# 09-RTL8111H-2.net
KiCad netlist of a schematic drawn in Altium Designer
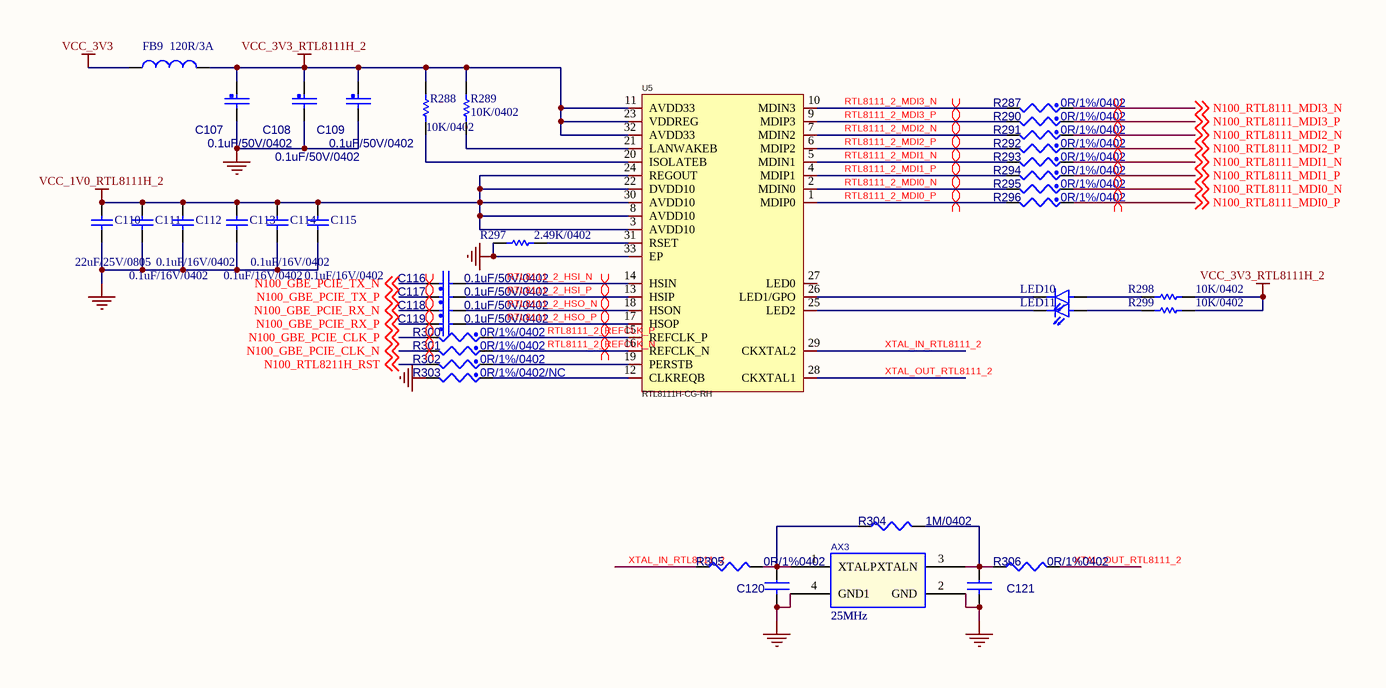
[diagram p0: 09-RTL8111H-2.schdoc]

(export (version "E")
  (design (tool "Eeschema 10.0.6"))
  (components
    (comp (ref "AX3")
      (value "25MHz")
      (footprint "2016")
      (fields (field (name "ALTIUM_VALUE") "25MHz"))
      (libsource (lib "*") (part "XTAL_0"))
    )
    (comp (ref "C107")
      (value "0.1uF/50V/0402")
      (footprint "C0402")
      (description "GCM155R71H104KE02/MURATA")
      (fields (field (name "TOLERANCE") "10%") (field (name "VOLTAGE") "16V"))
      (libsource (lib "*") (part "CAP_NP"))
    )
    (comp (ref "C108")
      (value "0.1uF/50V/0402")
      (footprint "C0402")
      (description "GCM155R71H104KE02/MURATA")
      (fields (field (name "TOLERANCE") "10%") (field (name "VOLTAGE") "16V"))
      (libsource (lib "*") (part "CAP_NP"))
    )
    (comp (ref "C109")
      (value "0.1uF/50V/0402")
      (footprint "C0402")
      (description "GCM155R71H104KE02/MURATA")
      (fields (field (name "TOLERANCE") "10%") (field (name "VOLTAGE") "16V"))
      (libsource (lib "*") (part "CAP_NP"))
    )
    (comp (ref "C110")
      (value "22uF/25V/0805")
      (description "Capacitor")
      (fields (field (name "PUBLISHER") "Altium Limited"))
      (libsource (lib "LIBS") (part "CAP"))
    )
    (comp (ref "C111")
      (value "0.1uF/16V/0402")
      (description "Capacitor")
      (fields (field (name "PUBLISHER") "Altium Limited"))
      (libsource (lib "LIBS") (part "CAP"))
    )
    (comp (ref "C112")
      (value "0.1uF/16V/0402")
      (description "Capacitor")
      (fields (field (name "PUBLISHER") "Altium Limited"))
      (libsource (lib "LIBS") (part "CAP"))
    )
    (comp (ref "C113")
      (value "0.1uF/16V/0402")
      (description "Capacitor")
      (fields (field (name "PUBLISHER") "Altium Limited"))
      (libsource (lib "LIBS") (part "CAP"))
    )
    (comp (ref "C114")
      (value "0.1uF/16V/0402")
      (description "Capacitor")
      (fields (field (name "PUBLISHER") "Altium Limited"))
      (libsource (lib "LIBS") (part "CAP"))
    )
    (comp (ref "C115")
      (value "0.1uF/16V/0402")
      (description "Capacitor")
      (fields (field (name "PUBLISHER") "Altium Limited"))
      (libsource (lib "LIBS") (part "CAP"))
    )
    (comp (ref "C116")
      (value "0.1uF/50V/0402")
      (footprint "C0402")
      (description "GCM155R71H104KE02/MURATA")
      (fields (field (name "TOLERANCE") "10%") (field (name "VOLTAGE") "16V"))
      (libsource (lib "*") (part "CAP_NP"))
    )
    (comp (ref "C117")
      (value "0.1uF/50V/0402")
      (footprint "C0402")
      (description "GCM155R71H104KE02/MURATA")
      (fields (field (name "TOLERANCE") "10%") (field (name "VOLTAGE") "16V"))
      (libsource (lib "*") (part "CAP_NP"))
    )
    (comp (ref "C118")
      (value "0.1uF/50V/0402")
      (footprint "C0402")
      (description "GCM155R71H104KE02/MURATA")
      (fields (field (name "TOLERANCE") "10%") (field (name "VOLTAGE") "16V"))
      (libsource (lib "*") (part "CAP_NP"))
    )
    (comp (ref "C119")
      (value "0.1uF/50V/0402")
      (footprint "C0402")
      (description "GCM155R71H104KE02/MURATA")
      (fields (field (name "TOLERANCE") "10%") (field (name "VOLTAGE") "16V"))
      (libsource (lib "*") (part "CAP_NP"))
    )
    (comp (ref "C120") (value "CAP NP_Dup3") (footprint "C0402") (libsource (lib "*") (part "CAP NP_Dup3")))
    (comp (ref "C121") (value "CAP NP_Dup3") (footprint "C0402") (libsource (lib "*") (part "CAP NP_Dup3")))
    (comp (ref "FB9")
      (value "120R/3A")
      (footprint "L0603")
      (description "BLM18KG121TN1D")
      (fields (field (name "PUBLISHER") "Altium Limited"))
      (libsource (lib "LIBS") (part "Inductor"))
    )
    (comp (ref "LED10") (value "LED_GREEN") (footprint "LED0603") (libsource (lib "LIBS") (part "LED")))
    (comp (ref "LED11") (value "LED_GREEN") (footprint "LED0603") (libsource (lib "LIBS") (part "LED")))
    (comp (ref "R287")
      (value "0R/1%/0402")
      (footprint "R0402")
      (description "AC0402FR-070RL/YAGEO")
      (fields (field (name "TOLERANCE") "1%") (field (name "Comment") "RES_Dup2"))
      (libsource (lib "*") (part "RES_Dup2"))
    )
    (comp (ref "R288")
      (value "10K/0402")
      (footprint "R0402")
      (description "Semiconductor Resistor")
      (fields (field (name "PUBLISHER") "Altium Limited"))
      (libsource (lib "LIBS") (part "Res Semi"))
    )
    (comp (ref "R289")
      (value "10K/0402")
      (footprint "R0402")
      (description "Semiconductor Resistor")
      (fields (field (name "PUBLISHER") "Altium Limited"))
      (libsource (lib "LIBS") (part "Res Semi"))
    )
    (comp (ref "R290")
      (value "0R/1%/0402")
      (footprint "R0402")
      (description "AC0402FR-070RL/YAGEO")
      (fields (field (name "TOLERANCE") "1%") (field (name "Comment") "RES_Dup2"))
      (libsource (lib "*") (part "RES_Dup2"))
    )
    (comp (ref "R291")
      (value "0R/1%/0402")
      (footprint "R0402")
      (description "AC0402FR-070RL/YAGEO")
      (fields (field (name "TOLERANCE") "1%") (field (name "Comment") "RES_Dup2"))
      (libsource (lib "*") (part "RES_Dup2"))
    )
    (comp (ref "R292")
      (value "0R/1%/0402")
      (footprint "R0402")
      (description "AC0402FR-070RL/YAGEO")
      (fields (field (name "TOLERANCE") "1%") (field (name "Comment") "RES_Dup2"))
      (libsource (lib "*") (part "RES_Dup2"))
    )
    (comp (ref "R293")
      (value "0R/1%/0402")
      (footprint "R0402")
      (description "AC0402FR-070RL/YAGEO")
      (fields (field (name "TOLERANCE") "1%") (field (name "Comment") "RES_Dup2"))
      (libsource (lib "*") (part "RES_Dup2"))
    )
    (comp (ref "R294")
      (value "0R/1%/0402")
      (footprint "R0402")
      (description "AC0402FR-070RL/YAGEO")
      (fields (field (name "TOLERANCE") "1%") (field (name "Comment") "RES_Dup2"))
      (libsource (lib "*") (part "RES_Dup2"))
    )
    (comp (ref "R295")
      (value "0R/1%/0402")
      (footprint "R0402")
      (description "AC0402FR-070RL/YAGEO")
      (fields (field (name "TOLERANCE") "1%") (field (name "Comment") "RES_Dup2"))
      (libsource (lib "*") (part "RES_Dup2"))
    )
    (comp (ref "R296")
      (value "0R/1%/0402")
      (footprint "R0402")
      (description "AC0402FR-070RL/YAGEO")
      (fields (field (name "TOLERANCE") "1%") (field (name "Comment") "RES_Dup2"))
      (libsource (lib "*") (part "RES_Dup2"))
    )
    (comp (ref "R297")
      (value "2.49K/0402")
      (footprint "R0402")
      (description "Semiconductor Resistor")
      (fields (field (name "PUBLISHER") "Altium Limited"))
      (libsource (lib "LIBS") (part "Res Semi"))
    )
    (comp (ref "R298")
      (value "10K/0402")
      (footprint "R0402")
      (description "Semiconductor Resistor")
      (fields (field (name "PUBLISHER") "Altium Limited"))
      (libsource (lib "LIBS") (part "Res Semi"))
    )
    (comp (ref "R299")
      (value "10K/0402")
      (footprint "R0402")
      (description "Semiconductor Resistor")
      (fields (field (name "PUBLISHER") "Altium Limited"))
      (libsource (lib "LIBS") (part "Res Semi"))
    )
    (comp (ref "R300")
      (value "0R/1%/0402")
      (footprint "R0402")
      (description "AC0402FR-070RL/YAGEO")
      (fields (field (name "TOLERANCE") "1%") (field (name "Comment") "RES_Dup2"))
      (libsource (lib "*") (part "RES_Dup2"))
    )
    (comp (ref "R301")
      (value "0R/1%/0402")
      (footprint "R0402")
      (description "AC0402FR-070RL/YAGEO")
      (fields (field (name "TOLERANCE") "1%") (field (name "Comment") "RES_Dup2"))
      (libsource (lib "*") (part "RES_Dup2"))
    )
    (comp (ref "R302")
      (value "0R/1%/0402")
      (footprint "R0402")
      (description "AC0402FR-070RL/YAGEO")
      (fields (field (name "TOLERANCE") "1%") (field (name "Comment") "RES_Dup2"))
      (libsource (lib "*") (part "RES_Dup2"))
    )
    (comp (ref "R303")
      (value "0R/1%/0402/NC")
      (footprint "R0402")
      (description "AC0402FR-070RL/YAGEO")
      (fields (field (name "TOLERANCE") "1%") (field (name "Comment") "RES_Dup2"))
      (libsource (lib "*") (part "RES_Dup2"))
    )
    (comp (ref "R304")
      (value "1M/0402")
      (footprint "R0402")
      (fields (field (name "Comment") "R_Dup3"))
      (libsource (lib "*") (part "R_Dup3"))
    )
    (comp (ref "R305")
      (value "0R/1%0402")
      (footprint "R0402")
      (fields (field (name "Comment") "R_Dup3"))
      (libsource (lib "*") (part "R_Dup3"))
    )
    (comp (ref "R306")
      (value "0R/1%0402")
      (footprint "R0402")
      (fields (field (name "Comment") "R_Dup3"))
      (libsource (lib "*") (part "R_Dup3"))
    )
    (comp (ref "U5")
      (value "RTL8111H-CG-RH")
      (footprint "RTL8111H-CG-RH")
      (fields (field (name "MANUFACTURER") "REALTEK(瑞昱)") (field (name "MANUFACTURER PART") "RTL8111H-CG"))
      (libsource (lib "17267508141_1726750814") (part "RTL8111H-CG"))
    )
  )
  (nets
    (net (code "1") (name "/RTL8111_2_HSI_N") (class "Default")
      (node (ref "C116") (pin "2") (pinfunction "2_2") (pintype "passive"))
      (node (ref "U5") (pin "14") (pinfunction "HSIN_14") (pintype "passive"))
    )
    (net (code "2") (name "/RTL8111_2_HSI_P") (class "Default")
      (node (ref "C117") (pin "2") (pinfunction "2_2") (pintype "passive"))
      (node (ref "U5") (pin "13") (pinfunction "HSIP_13") (pintype "passive"))
    )
    (net (code "3") (name "/RTL8111_2_HSO_N") (class "Default")
      (node (ref "C118") (pin "2") (pinfunction "2_2") (pintype "passive"))
      (node (ref "U5") (pin "18") (pinfunction "HSON_18") (pintype "passive"))
    )
    (net (code "4") (name "/RTL8111_2_HSO_P") (class "Default")
      (node (ref "C119") (pin "2") (pinfunction "2_2") (pintype "passive"))
      (node (ref "U5") (pin "17") (pinfunction "HSOP_17") (pintype "passive"))
    )
    (net (code "5") (name "/RTL8111_2_MDI0_N") (class "Default")
      (node (ref "R295") (pin "2") (pinfunction "2_2") (pintype "passive"))
      (node (ref "U5") (pin "2") (pinfunction "MDIN0_2") (pintype "passive"))
    )
    (net (code "6") (name "/RTL8111_2_MDI0_P") (class "Default")
      (node (ref "R296") (pin "2") (pinfunction "2_2") (pintype "passive"))
      (node (ref "U5") (pin "1") (pinfunction "MDIP0_1") (pintype "passive"))
    )
    (net (code "7") (name "/RTL8111_2_MDI1_N") (class "Default")
      (node (ref "R293") (pin "2") (pinfunction "2_2") (pintype "passive"))
      (node (ref "U5") (pin "5") (pinfunction "MDIN1_5") (pintype "passive"))
    )
    (net (code "8") (name "/RTL8111_2_MDI1_P") (class "Default")
      (node (ref "R294") (pin "2") (pinfunction "2_2") (pintype "passive"))
      (node (ref "U5") (pin "4") (pinfunction "MDIP1_4") (pintype "passive"))
    )
    (net (code "9") (name "/RTL8111_2_MDI2_N") (class "Default")
      (node (ref "R291") (pin "2") (pinfunction "2_2") (pintype "passive"))
      (node (ref "U5") (pin "7") (pinfunction "MDIN2_7") (pintype "passive"))
    )
    (net (code "10") (name "/RTL8111_2_MDI2_P") (class "Default")
      (node (ref "R292") (pin "2") (pinfunction "2_2") (pintype "passive"))
      (node (ref "U5") (pin "6") (pinfunction "MDIP2_6") (pintype "passive"))
    )
    (net (code "11") (name "/RTL8111_2_MDI3_N") (class "Default")
      (node (ref "R287") (pin "2") (pinfunction "2_2") (pintype "passive"))
      (node (ref "U5") (pin "10") (pinfunction "MDIN3_10") (pintype "passive"))
    )
    (net (code "12") (name "/RTL8111_2_MDI3_P") (class "Default")
      (node (ref "R290") (pin "2") (pinfunction "2_2") (pintype "passive"))
      (node (ref "U5") (pin "9") (pinfunction "MDIP3_9") (pintype "passive"))
    )
    (net (code "13") (name "/RTL8111_2_REFCLK_N") (class "Default")
      (node (ref "R301") (pin "1") (pinfunction "1_1") (pintype "passive"))
      (node (ref "U5") (pin "16") (pinfunction "REFCLK_N_16") (pintype "passive"))
    )
    (net (code "14") (name "/RTL8111_2_REFCLK_P") (class "Default")
      (node (ref "R300") (pin "1") (pinfunction "1_1") (pintype "passive"))
      (node (ref "U5") (pin "15") (pinfunction "REFCLK_P_15") (pintype "passive"))
    )
    (net (code "15") (name "/XTAL_IN_RTL8111_2") (class "Default")
      (node (ref "R305") (pin "1") (pinfunction "1_1") (pintype "passive"))
      (node (ref "U5") (pin "29") (pinfunction "CKXTAL2_29") (pintype "passive"))
    )
    (net (code "16") (name "/XTAL_OUT_RTL8111_2") (class "Default")
      (node (ref "R306") (pin "2") (pinfunction "2_2") (pintype "passive"))
      (node (ref "U5") (pin "28") (pinfunction "CKXTAL1_28") (pintype "passive"))
    )
    (net (code "17") (name "GND") (class "Default")
      (node (ref "AX3") (pin "2") (pinfunction "GND_2") (pintype "passive"))
      (node (ref "AX3") (pin "4") (pinfunction "GND1_4") (pintype "passive"))
      (node (ref "C107") (pin "2") (pinfunction "2_2") (pintype "passive"))
      (node (ref "C108") (pin "2") (pinfunction "2_2") (pintype "passive"))
      (node (ref "C109") (pin "2") (pinfunction "2_2") (pintype "passive"))
      (node (ref "C110") (pin "1") (pinfunction "1_1") (pintype "passive"))
      (node (ref "C111") (pin "1") (pinfunction "1_1") (pintype "passive"))
      (node (ref "C112") (pin "1") (pinfunction "1_1") (pintype "passive"))
      (node (ref "C113") (pin "1") (pinfunction "1_1") (pintype "passive"))
      (node (ref "C114") (pin "1") (pinfunction "1_1") (pintype "passive"))
      (node (ref "C115") (pin "1") (pinfunction "1_1") (pintype "passive"))
      (node (ref "C120") (pin "2") (pinfunction "2_2") (pintype "passive"))
      (node (ref "C121") (pin "2") (pinfunction "2_2") (pintype "passive"))
      (node (ref "R297") (pin "1") (pinfunction "1_1") (pintype "passive"))
      (node (ref "R303") (pin "2") (pinfunction "2_2") (pintype "passive"))
      (node (ref "U5") (pin "33") (pinfunction "EP_33") (pintype "passive"))
    )
    (net (code "18") (name "N100_GBE_PCIE_CLK_N") (class "Default")
      (node (ref "R301") (pin "2") (pinfunction "2_2") (pintype "passive"))
    )
    (net (code "19") (name "N100_GBE_PCIE_CLK_P") (class "Default")
      (node (ref "R300") (pin "2") (pinfunction "2_2") (pintype "passive"))
    )
    (net (code "20") (name "N100_GBE_PCIE_RX_N") (class "Default")
      (node (ref "C118") (pin "1") (pinfunction "1_1") (pintype "passive"))
    )
    (net (code "21") (name "N100_GBE_PCIE_RX_P") (class "Default")
      (node (ref "C119") (pin "1") (pinfunction "1_1") (pintype "passive"))
    )
    (net (code "22") (name "N100_GBE_PCIE_TX_N") (class "Default")
      (node (ref "C116") (pin "1") (pinfunction "1_1") (pintype "passive"))
    )
    (net (code "23") (name "N100_GBE_PCIE_TX_P") (class "Default")
      (node (ref "C117") (pin "1") (pinfunction "1_1") (pintype "passive"))
    )
    (net (code "24") (name "N100_RTL8111_MDI0_N") (class "Default")
      (node (ref "R295") (pin "1") (pinfunction "1_1") (pintype "passive"))
    )
    (net (code "25") (name "N100_RTL8111_MDI0_P") (class "Default")
      (node (ref "R296") (pin "1") (pinfunction "1_1") (pintype "passive"))
    )
    (net (code "26") (name "N100_RTL8111_MDI1_N") (class "Default")
      (node (ref "R293") (pin "1") (pinfunction "1_1") (pintype "passive"))
    )
    (net (code "27") (name "N100_RTL8111_MDI1_P") (class "Default")
      (node (ref "R294") (pin "1") (pinfunction "1_1") (pintype "passive"))
    )
    (net (code "28") (name "N100_RTL8111_MDI2_N") (class "Default")
      (node (ref "R291") (pin "1") (pinfunction "1_1") (pintype "passive"))
    )
    (net (code "29") (name "N100_RTL8111_MDI2_P") (class "Default")
      (node (ref "R292") (pin "1") (pinfunction "1_1") (pintype "passive"))
    )
    (net (code "30") (name "N100_RTL8111_MDI3_N") (class "Default")
      (node (ref "R287") (pin "1") (pinfunction "1_1") (pintype "passive"))
    )
    (net (code "31") (name "N100_RTL8111_MDI3_P") (class "Default")
      (node (ref "R290") (pin "1") (pinfunction "1_1") (pintype "passive"))
    )
    (net (code "32") (name "N100_RTL8211H_RST") (class "Default")
      (node (ref "R302") (pin "2") (pinfunction "2_2") (pintype "passive"))
    )
    (net (code "33") (name "Net-(AX3-XTALN)") (class "Default")
      (node (ref "AX3") (pin "3") (pinfunction "XTALN_3") (pintype "passive"))
      (node (ref "C121") (pin "1") (pinfunction "1_1") (pintype "passive"))
      (node (ref "R304") (pin "2") (pinfunction "2_2") (pintype "passive"))
      (node (ref "R306") (pin "1") (pinfunction "1_1") (pintype "passive"))
    )
    (net (code "34") (name "Net-(AX3-XTALP)") (class "Default")
      (node (ref "AX3") (pin "1") (pinfunction "XTALP_1") (pintype "passive"))
      (node (ref "C120") (pin "1") (pinfunction "1_1") (pintype "passive"))
      (node (ref "R304") (pin "1") (pinfunction "1_1") (pintype "passive"))
      (node (ref "R305") (pin "2") (pinfunction "2_2") (pintype "passive"))
    )
    (net (code "35") (name "Net-(LED10-Pad1)") (class "Default")
      (node (ref "LED10") (pin "1") (pinfunction "1_1") (pintype "passive"))
      (node (ref "R298") (pin "2") (pinfunction "2_2") (pintype "passive"))
    )
    (net (code "36") (name "Net-(LED11-Pad1)") (class "Default")
      (node (ref "LED11") (pin "1") (pinfunction "1_1") (pintype "passive"))
      (node (ref "R299") (pin "2") (pinfunction "2_2") (pintype "passive"))
    )
    (net (code "37") (name "Net-(U5-CLKREQB)") (class "Default")
      (node (ref "R303") (pin "1") (pinfunction "1_1") (pintype "passive"))
      (node (ref "U5") (pin "12") (pinfunction "CLKREQB_12") (pintype "passive"))
    )
    (net (code "38") (name "Net-(U5-ISOLATEB)") (class "Default")
      (node (ref "R288") (pin "2") (pinfunction "2_2") (pintype "passive"))
      (node (ref "U5") (pin "20") (pinfunction "ISOLATEB_20") (pintype "passive"))
    )
    (net (code "39") (name "Net-(U5-LANWAKEB)") (class "Default")
      (node (ref "R289") (pin "2") (pinfunction "2_2") (pintype "passive"))
      (node (ref "U5") (pin "21") (pinfunction "LANWAKEB_21") (pintype "passive"))
    )
    (net (code "40") (name "Net-(U5-LED1{slash}GPO)") (class "Default")
      (node (ref "LED10") (pin "2") (pinfunction "2_2") (pintype "passive"))
      (node (ref "U5") (pin "26") (pinfunction "LED1/GPO_26") (pintype "passive"))
    )
    (net (code "41") (name "Net-(U5-LED2)") (class "Default")
      (node (ref "LED11") (pin "2") (pinfunction "2_2") (pintype "passive"))
      (node (ref "U5") (pin "25") (pinfunction "LED2_25") (pintype "passive"))
    )
    (net (code "42") (name "Net-(U5-PERSTB)") (class "Default")
      (node (ref "R302") (pin "1") (pinfunction "1_1") (pintype "passive"))
      (node (ref "U5") (pin "19") (pinfunction "PERSTB_19") (pintype "passive"))
    )
    (net (code "43") (name "Net-(U5-RSET)") (class "Default")
      (node (ref "R297") (pin "2") (pinfunction "2_2") (pintype "passive"))
      (node (ref "U5") (pin "31") (pinfunction "RSET_31") (pintype "passive"))
    )
    (net (code "44") (name "VCC_1V0_RTL8111H_2") (class "Default")
      (node (ref "C110") (pin "2") (pinfunction "2_2") (pintype "passive"))
      (node (ref "C111") (pin "2") (pinfunction "2_2") (pintype "passive"))
      (node (ref "C112") (pin "2") (pinfunction "2_2") (pintype "passive"))
      (node (ref "C113") (pin "2") (pinfunction "2_2") (pintype "passive"))
      (node (ref "C114") (pin "2") (pinfunction "2_2") (pintype "passive"))
      (node (ref "C115") (pin "2") (pinfunction "2_2") (pintype "passive"))
      (node (ref "U5") (pin "22") (pinfunction "DVDD10_22") (pintype "passive"))
      (node (ref "U5") (pin "24") (pinfunction "REGOUT_24") (pintype "passive"))
      (node (ref "U5") (pin "3") (pinfunction "AVDD10_3") (pintype "passive"))
      (node (ref "U5") (pin "30") (pinfunction "AVDD10_30") (pintype "passive"))
      (node (ref "U5") (pin "8") (pinfunction "AVDD10_8") (pintype "passive"))
    )
    (net (code "45") (name "VCC_3V3") (class "Default")
      (node (ref "FB9") (pin "1") (pinfunction "1_1") (pintype "passive"))
    )
    (net (code "46") (name "VCC_3V3_RTL8111H_2") (class "Default")
      (node (ref "C107") (pin "1") (pinfunction "1_1") (pintype "passive"))
      (node (ref "C108") (pin "1") (pinfunction "1_1") (pintype "passive"))
      (node (ref "C109") (pin "1") (pinfunction "1_1") (pintype "passive"))
      (node (ref "FB9") (pin "2") (pinfunction "2_2") (pintype "passive"))
      (node (ref "R288") (pin "1") (pinfunction "1_1") (pintype "passive"))
      (node (ref "R289") (pin "1") (pinfunction "1_1") (pintype "passive"))
      (node (ref "R298") (pin "1") (pinfunction "1_1") (pintype "passive"))
      (node (ref "R299") (pin "1") (pinfunction "1_1") (pintype "passive"))
      (node (ref "U5") (pin "11") (pinfunction "AVDD33_11") (pintype "passive"))
      (node (ref "U5") (pin "23") (pinfunction "VDDREG_23") (pintype "passive"))
      (node (ref "U5") (pin "32") (pinfunction "AVDD33_32") (pintype "passive"))
    )
    (net (code "47") (name "unconnected-(U5-LED0-Pad27)") (class "Default")
      (node (ref "U5") (pin "27") (pinfunction "LED0_27") (pintype "passive"))
    )
  )
)
